# lna-balun.net
KiCad netlist of a schematic drawn in Altium Designer
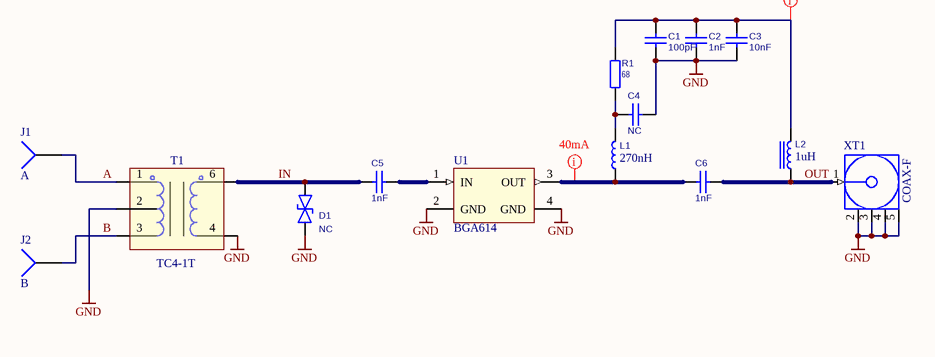
[diagram p0: lna-balun.SchDoc]

(export (version "E")
  (design (tool "Eeschema 10.0.6"))
  (components
    (comp (ref "C1")
      (value "100pF")
      (footprint "Capacitors:C0805")
      (description "CAP_NPOL")
      (libsource (lib "capacitors") (part "CAP_NPOL"))
    )
    (comp (ref "C2")
      (value "1nF")
      (footprint "Capacitors:C0805")
      (description "CAP_NPOL")
      (libsource (lib "capacitors") (part "CAP_NPOL"))
    )
    (comp (ref "C3")
      (value "10nF")
      (footprint "Capacitors:C0805")
      (description "CAP_NPOL")
      (libsource (lib "capacitors") (part "CAP_NPOL"))
    )
    (comp (ref "C4")
      (value "NC")
      (footprint "Capacitors:C0805")
      (description "CAP_NPOL")
      (libsource (lib "capacitors") (part "CAP_NPOL"))
    )
    (comp (ref "C5")
      (value "1nF")
      (footprint "C1210")
      (description "CAP_NPOL")
      (libsource (lib "capacitors") (part "CAP_NPOL"))
    )
    (comp (ref "C6")
      (value "1nF")
      (footprint "C1210")
      (description "CAP_NPOL")
      (libsource (lib "capacitors") (part "CAP_NPOL"))
    )
    (comp (ref "D1")
      (value "NC")
      (footprint "SOD-323")
      (description "TVS Diodes")
      (libsource (lib "diodes") (part "TVS_BIDIR"))
    )
    (comp (ref "J1")
      (value "A")
      (footprint "PIN1")
      (description "Socket")
      (fields (field (name "PUBLISHER") "Altium Limited"))
      (libsource (lib "Miscellaneous Connectors") (part "Socket"))
    )
    (comp (ref "J2")
      (value "B")
      (footprint "PIN1")
      (description "Socket")
      (fields (field (name "PUBLISHER") "Altium Limited"))
      (libsource (lib "Miscellaneous Connectors") (part "Socket"))
    )
    (comp (ref "L1")
      (value "270nH")
      (footprint "IND0603")
      (description "IND_WO_IRON")
      (libsource (lib "inductors") (part "IND_WO_IRON"))
    )
    (comp (ref "L2")
      (value "1uH")
      (footprint "IND0603")
      (description "IND_W_IRON")
      (libsource (lib "inductors") (part "IND_W_IRON"))
    )
    (comp (ref "R1")
      (value "68")
      (footprint "Resistors:R0805")
      (description "RES")
      (libsource (lib "resistors") (part "RESISTOR"))
    )
    (comp (ref "T1")
      (value "TC4-1T")
      (footprint "AT224")
      (description "RF TRANSFORMERS WIDEBAND")
      (libsource (lib "TR-RF-WB") (part "TC4-1T"))
    )
    (comp (ref "U1")
      (value "BGA614")
      (footprint "SOT-343")
      (description "Silicon Germanium Broadband MMIC Amplifier")
      (libsource (lib "BGA614") (part "BGA614"))
    )
    (comp (ref "XT1")
      (value "COAX-F")
      (footprint "RF:SMA-16")
      (fields (field (name "PUBLISHER") "Altium Limited"))
      (libsource (lib "Miscellaneous Connectors") (part "COAX-F"))
    )
  )
  (nets
    (net (code "1") (name "/A") (class "Default")
      (node (ref "J1") (pin "1") (pinfunction "1_1") (pintype "passive"))
      (node (ref "T1") (pin "1") (pinfunction "1_1") (pintype "passive"))
    )
    (net (code "2") (name "/B") (class "Default")
      (node (ref "J2") (pin "1") (pinfunction "1_1") (pintype "passive"))
      (node (ref "T1") (pin "3") (pinfunction "3_3") (pintype "passive"))
    )
    (net (code "3") (name "/IN") (class "Default")
      (node (ref "C5") (pin "1") (pinfunction "1_1") (pintype "passive"))
      (node (ref "D1") (pin "2") (pinfunction "2_2") (pintype "passive"))
      (node (ref "T1") (pin "6") (pinfunction "6_6") (pintype "passive"))
    )
    (net (code "4") (name "/OUT") (class "Default")
      (node (ref "C6") (pin "2") (pinfunction "2_2") (pintype "passive"))
      (node (ref "L2") (pin "1") (pintype "passive"))
      (node (ref "XT1") (pin "1") (pinfunction "Signal_1") (pintype "input"))
    )
    (net (code "5") (name "GND") (class "Default")
      (node (ref "C1") (pin "1") (pinfunction "1_1") (pintype "passive"))
      (node (ref "C2") (pin "1") (pinfunction "1_1") (pintype "passive"))
      (node (ref "C3") (pin "1") (pinfunction "1_1") (pintype "passive"))
      (node (ref "C4") (pin "2") (pinfunction "2_2") (pintype "passive"))
      (node (ref "D1") (pin "1") (pinfunction "1_1") (pintype "passive"))
      (node (ref "T1") (pin "2") (pinfunction "2_2") (pintype "passive"))
      (node (ref "T1") (pin "4") (pinfunction "4_4") (pintype "passive"))
      (node (ref "U1") (pin "2") (pinfunction "GND_2") (pintype "power_in"))
      (node (ref "U1") (pin "4") (pinfunction "GND_4") (pintype "power_in"))
      (node (ref "XT1") (pin "2") (pinfunction "GND_2") (pintype "power_in"))
      (node (ref "XT1") (pin "3") (pinfunction "GND_3") (pintype "power_in"))
      (node (ref "XT1") (pin "4") (pinfunction "GND_4") (pintype "power_in"))
      (node (ref "XT1") (pin "5") (pinfunction "GND_5") (pintype "power_in"))
    )
    (net (code "6") (name "Net-(C1-Pad2)") (class "Default")
      (node (ref "C1") (pin "2") (pinfunction "2_2") (pintype "passive"))
      (node (ref "C2") (pin "2") (pinfunction "2_2") (pintype "passive"))
      (node (ref "C3") (pin "2") (pinfunction "2_2") (pintype "passive"))
      (node (ref "L2") (pin "2") (pintype "passive"))
      (node (ref "R1") (pin "2") (pinfunction "2_2") (pintype "passive"))
    )
    (net (code "7") (name "Net-(C4-Pad1)") (class "Default")
      (node (ref "C4") (pin "1") (pinfunction "1_1") (pintype "passive"))
      (node (ref "L1") (pin "2") (pintype "passive"))
      (node (ref "R1") (pin "1") (pinfunction "1_1") (pintype "passive"))
    )
    (net (code "8") (name "Net-(U1-IN)") (class "Default")
      (node (ref "C5") (pin "2") (pinfunction "2_2") (pintype "passive"))
      (node (ref "U1") (pin "1") (pinfunction "IN_1") (pintype "input"))
    )
    (net (code "9") (name "Net-(U1-OUT)") (class "Default")
      (node (ref "C6") (pin "1") (pinfunction "1_1") (pintype "passive"))
      (node (ref "L1") (pin "1") (pintype "passive"))
      (node (ref "U1") (pin "3") (pinfunction "OUT_3") (pintype "output"))
    )
  )
)
